# Batterij.net
KiCad netlist of a schematic drawn in Altium Designer
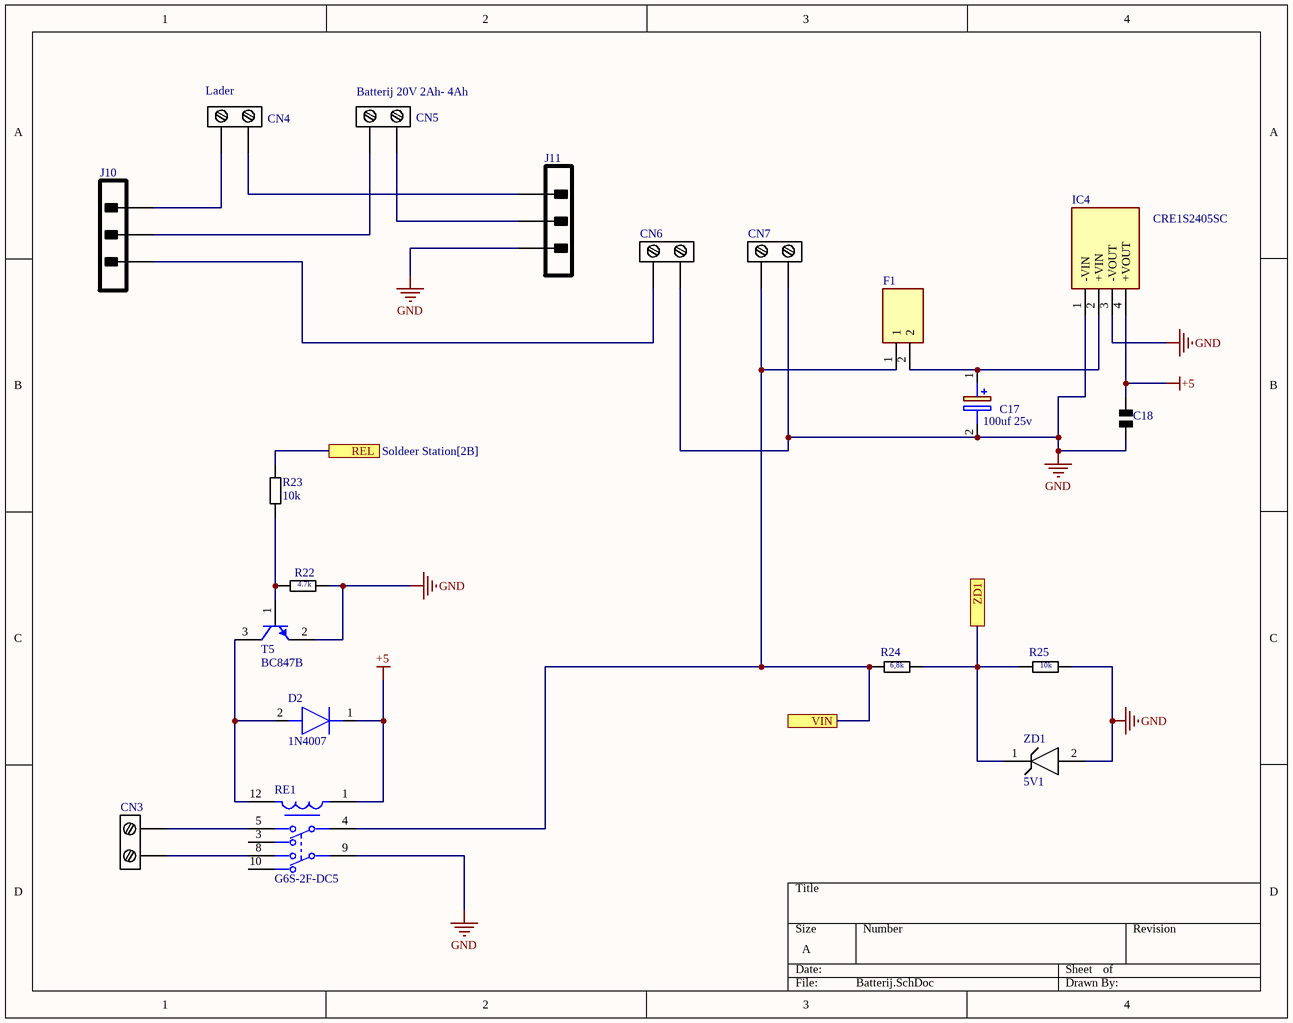
[diagram p0: Batterij.SchDoc]

(export (version "E")
  (design (tool "Eeschema 10.0.6"))
  (components
    (comp (ref "C17")
      (value "100uf 25v")
      (footprint "100uf 25v")
      (description "Capacitor Polarised")
      (fields
        (field (name "MANUFACTURER_PART_NUMBER") "ESMG250ELL101MF11D")
        (field (name "MOUSER PART NUMBER") "661-ESMG250ELL101MF")
      )
      (libsource (lib "Soldeer Station Library") (part "100uf 25v"))
    )
    (comp (ref "C18")
      (value "C0402C104K4RACTU")
      (footprint "Capacitor")
      (fields (field (name "MANUFACTURER") "Kemet"))
      (libsource (lib "Soldeer Station Library") (part "Condensator"))
    )
    (comp (ref "CN3")
      (value "K1,K2,K3,K8 Printkroonsteen")
      (footprint "K1,K2,K3,K8 Printkroonsteen")
      (fields (field (name "MF") "TE Connectivity") (field (name "MP") "282837-2"))
      (libsource (lib "Soldeer Station Library") (part "K1,K2,K3,K8 Printkroonsteen"))
    )
    (comp (ref "CN4")
      (value "Lader")
      (footprint "K1,K2,K3,K8 Printkroonsteen")
      (fields (field (name "MF") "TE Connectivity") (field (name "MP") "282837-2"))
      (libsource (lib "") (part "K1,K2,K3,K8 Printkroonsteen_1"))
    )
    (comp (ref "CN5")
      (value "Batterij 20V 2Ah- 4Ah")
      (footprint "K1,K2,K3,K8 Printkroonsteen")
      (fields (field (name "MF") "TE Connectivity") (field (name "MP") "282837-2"))
      (libsource (lib "") (part "K1,K2,K3,K8 Printkroonsteen_1"))
    )
    (comp (ref "CN6")
      (value "K1,K2,K3,K8 Printkroonsteen")
      (footprint "K1,K2,K3,K8 Printkroonsteen")
      (fields (field (name "MF") "TE Connectivity") (field (name "MP") "282837-2"))
      (libsource (lib "") (part "K1,K2,K3,K8 Printkroonsteen_1"))
    )
    (comp (ref "CN7")
      (value "K1,K2,K3,K8 Printkroonsteen")
      (footprint "K1,K2,K3,K8 Printkroonsteen")
      (fields (field (name "MF") "TE Connectivity") (field (name "MP") "282837-2"))
      (libsource (lib "") (part "K1,K2,K3,K8 Printkroonsteen_1"))
    )
    (comp (ref "D2")
      (value "1N4007")
      (footprint "1N4007")
      (description "Diode")
      (fields
        (field (name "MANUFACTURER_PART_NUMBER") "1N4007-E3/73")
        (field (name "MOUSER PART NUMBER") "625-1N4007-E3/73")
      )
      (libsource (lib "Soldeer Station Library") (part "1N4007"))
    )
    (comp (ref "F1")
      (value "~")
      (footprint "SamacSys:65800201009")
      (description "Hardware")
      (fields (field (name "MANUFACTURER_PART_NUMBER") "65800201009"))
      (libsource (lib "*") (part "65800201009"))
    )
    (comp (ref "IC4")
      (value "CRE1S2405SC")
      (footprint "SamacSys:CRE1(SC)")
      (description "Undefined or Miscellaneous")
      (fields (field (name "MOUSER PART NUMBER") "580-CRE1S2405SC"))
      (libsource (lib "*") (part "CRE1S2405SC"))
    )
    (comp (ref "J10")
      (value "K4,7,10 3Pinheader")
      (footprint "K4,7,10 3Pinheader")
      (libsource (lib "") (part "K4,7,10 3Pinheader_1"))
    )
    (comp (ref "J11")
      (value "K4,7,10 3Pinheader")
      (footprint "K4,7,10 3Pinheader")
      (libsource (lib "Soldeer Station Library") (part "K4,7,10 3Pinheader"))
    )
    (comp (ref "R22")
      (value "4.7k")
      (footprint "Resistor")
      (fields (field (name "MANUFACTURER") "Vishay Dale") (field (name "PART NUMBER") "CRCW08050000Z0EA"))
      (libsource (lib "Soldeer Station Library") (part "Resistor"))
    )
    (comp (ref "R23")
      (value "10k")
      (footprint "Resistor")
      (fields (field (name "MANUFACTURER") "Vishay Dale") (field (name "PART NUMBER") "CRCW08050000Z0EA"))
      (libsource (lib "Soldeer Station Library") (part "Resistor"))
    )
    (comp (ref "R24")
      (value "6,8k")
      (footprint "Resistor")
      (fields (field (name "MANUFACTURER") "Vishay Dale") (field (name "PART NUMBER") "CRCW08050000Z0EA"))
      (libsource (lib "Soldeer Station Library") (part "Resistor"))
    )
    (comp (ref "R25")
      (value "10k")
      (footprint "Resistor")
      (fields (field (name "MANUFACTURER") "Vishay Dale") (field (name "PART NUMBER") "CRCW08050000Z0EA"))
      (libsource (lib "Soldeer Station Library") (part "Resistor"))
    )
    (comp (ref "RE1")
      (value "G6S-2F-DC5")
      (footprint "G6S-2F-DC5")
      (fields
        (field (name "MANUFACTURER") "Omron")
        (field (name "OCTOPART") "https://octopart.com/g6s-2f-dc5-omron-85236")
      )
      (libsource (lib "Soldeer Station Library") (part "G6S-2F-DC5"))
    )
    (comp (ref "T5")
      (value "BC847B")
      (footprint "BC847B")
      (description "NPN Silicon AF Transistor")
      (fields (field (name "MANUFACTURER") "Infineon"))
      (libsource (lib "Soldeer Station Library") (part "BC847B"))
    )
    (comp (ref "ZD1")
      (value "5V1")
      (footprint "1N4007")
      (description "BZM55B5V1-TR")
      (libsource (lib "Soldeer Station Library") (part "Zenerdiode"))
    )
  )
  (nets
    (net (code "1") (name "+5") (class "Default")
      (node (ref "C18") (pin "2") (pinfunction "2_2") (pintype "passive"))
      (node (ref "D2") (pin "1") (pinfunction "K_1") (pintype "passive"))
      (node (ref "IC4") (pin "4") (pinfunction "+VOUT_4") (pintype "passive"))
      (node (ref "RE1") (pin "1") (pinfunction "1_1") (pintype "passive"))
    )
    (net (code "2") (name "/REL") (class "Default")
      (node (ref "R23") (pin "2") (pinfunction "2_2") (pintype "passive"))
    )
    (net (code "3") (name "/VIN") (class "Default")
      (node (ref "CN7") (pin "1") (pinfunction "1_1") (pintype "passive"))
      (node (ref "F1") (pin "1") (pinfunction "1_1") (pintype "passive"))
      (node (ref "R24") (pin "1") (pinfunction "1_1") (pintype "passive"))
      (node (ref "RE1") (pin "4") (pinfunction "4_4") (pintype "passive"))
    )
    (net (code "4") (name "/ZD1") (class "Default")
      (node (ref "R24") (pin "2") (pinfunction "2_2") (pintype "passive"))
      (node (ref "R25") (pin "1") (pinfunction "1_1") (pintype "passive"))
      (node (ref "ZD1") (pin "1") (pinfunction "C_1") (pintype "passive"))
    )
    (net (code "5") (name "GND") (class "Default")
      (node (ref "C17") (pin "2") (pinfunction "-_2") (pintype "passive"))
      (node (ref "C18") (pin "1") (pinfunction "1_1") (pintype "passive"))
      (node (ref "CN6") (pin "2") (pinfunction "2_2") (pintype "passive"))
      (node (ref "CN7") (pin "2") (pinfunction "2_2") (pintype "passive"))
      (node (ref "IC4") (pin "1") (pinfunction "-VIN_1") (pintype "passive"))
      (node (ref "IC4") (pin "3") (pinfunction "-VOUT_3") (pintype "passive"))
      (node (ref "J11") (pin "1") (pinfunction "1_1") (pintype "passive"))
      (node (ref "R22") (pin "2") (pinfunction "2_2") (pintype "passive"))
      (node (ref "R25") (pin "2") (pinfunction "2_2") (pintype "passive"))
      (node (ref "RE1") (pin "9") (pinfunction "9_9") (pintype "passive"))
      (node (ref "T5") (pin "2") (pinfunction "C_2") (pintype "passive"))
      (node (ref "ZD1") (pin "2") (pinfunction "A_2") (pintype "passive"))
    )
    (net (code "6") (name "Net-(C17-+)") (class "Default")
      (node (ref "C17") (pin "1") (pinfunction "+_1") (pintype "passive"))
      (node (ref "F1") (pin "2") (pinfunction "2_2") (pintype "passive"))
      (node (ref "IC4") (pin "2") (pinfunction "+VIN_2") (pintype "passive"))
    )
    (net (code "7") (name "Net-(CN3-Pad1)") (class "Default")
      (node (ref "CN3") (pin "1") (pinfunction "1_1") (pintype "passive"))
      (node (ref "RE1") (pin "8") (pinfunction "8_8") (pintype "passive"))
    )
    (net (code "8") (name "Net-(CN3-Pad2)") (class "Default")
      (node (ref "CN3") (pin "2") (pinfunction "2_2") (pintype "passive"))
      (node (ref "RE1") (pin "5") (pinfunction "5_5") (pintype "passive"))
    )
    (net (code "9") (name "Net-(CN4-Pad1)") (class "Default")
      (node (ref "CN4") (pin "1") (pinfunction "1_1") (pintype "passive"))
      (node (ref "J10") (pin "1") (pinfunction "1_1") (pintype "passive"))
    )
    (net (code "10") (name "Net-(CN4-Pad2)") (class "Default")
      (node (ref "CN4") (pin "2") (pinfunction "2_2") (pintype "passive"))
      (node (ref "J11") (pin "3") (pinfunction "3_3") (pintype "passive"))
    )
    (net (code "11") (name "Net-(CN5-Pad1)") (class "Default")
      (node (ref "CN5") (pin "1") (pinfunction "1_1") (pintype "passive"))
      (node (ref "J10") (pin "2") (pinfunction "2_2") (pintype "passive"))
    )
    (net (code "12") (name "Net-(CN5-Pad2)") (class "Default")
      (node (ref "CN5") (pin "2") (pinfunction "2_2") (pintype "passive"))
      (node (ref "J11") (pin "2") (pinfunction "2_2") (pintype "passive"))
    )
    (net (code "13") (name "Net-(CN6-Pad1)") (class "Default")
      (node (ref "CN6") (pin "1") (pinfunction "1_1") (pintype "passive"))
      (node (ref "J10") (pin "3") (pinfunction "3_3") (pintype "passive"))
    )
    (net (code "14") (name "Net-(D2-A)") (class "Default")
      (node (ref "D2") (pin "2") (pinfunction "A_2") (pintype "passive"))
      (node (ref "RE1") (pin "12") (pinfunction "12_12") (pintype "passive"))
      (node (ref "T5") (pin "3") (pinfunction "E_3") (pintype "passive"))
    )
    (net (code "15") (name "Net-(T5-B)") (class "Default")
      (node (ref "R22") (pin "1") (pinfunction "1_1") (pintype "passive"))
      (node (ref "R23") (pin "1") (pinfunction "1_1") (pintype "passive"))
      (node (ref "T5") (pin "1") (pinfunction "B_1") (pintype "passive"))
    )
    (net (code "16") (name "unconnected-(RE1-Pad3)") (class "Default")
      (node (ref "RE1") (pin "3") (pinfunction "3_3") (pintype "passive"))
    )
    (net (code "17") (name "unconnected-(RE1-Pad10)") (class "Default")
      (node (ref "RE1") (pin "10") (pinfunction "10_10") (pintype "passive"))
    )
  )
)
